# 4BUF_1.net
KiCad netlist of a schematic drawn in EAGLE
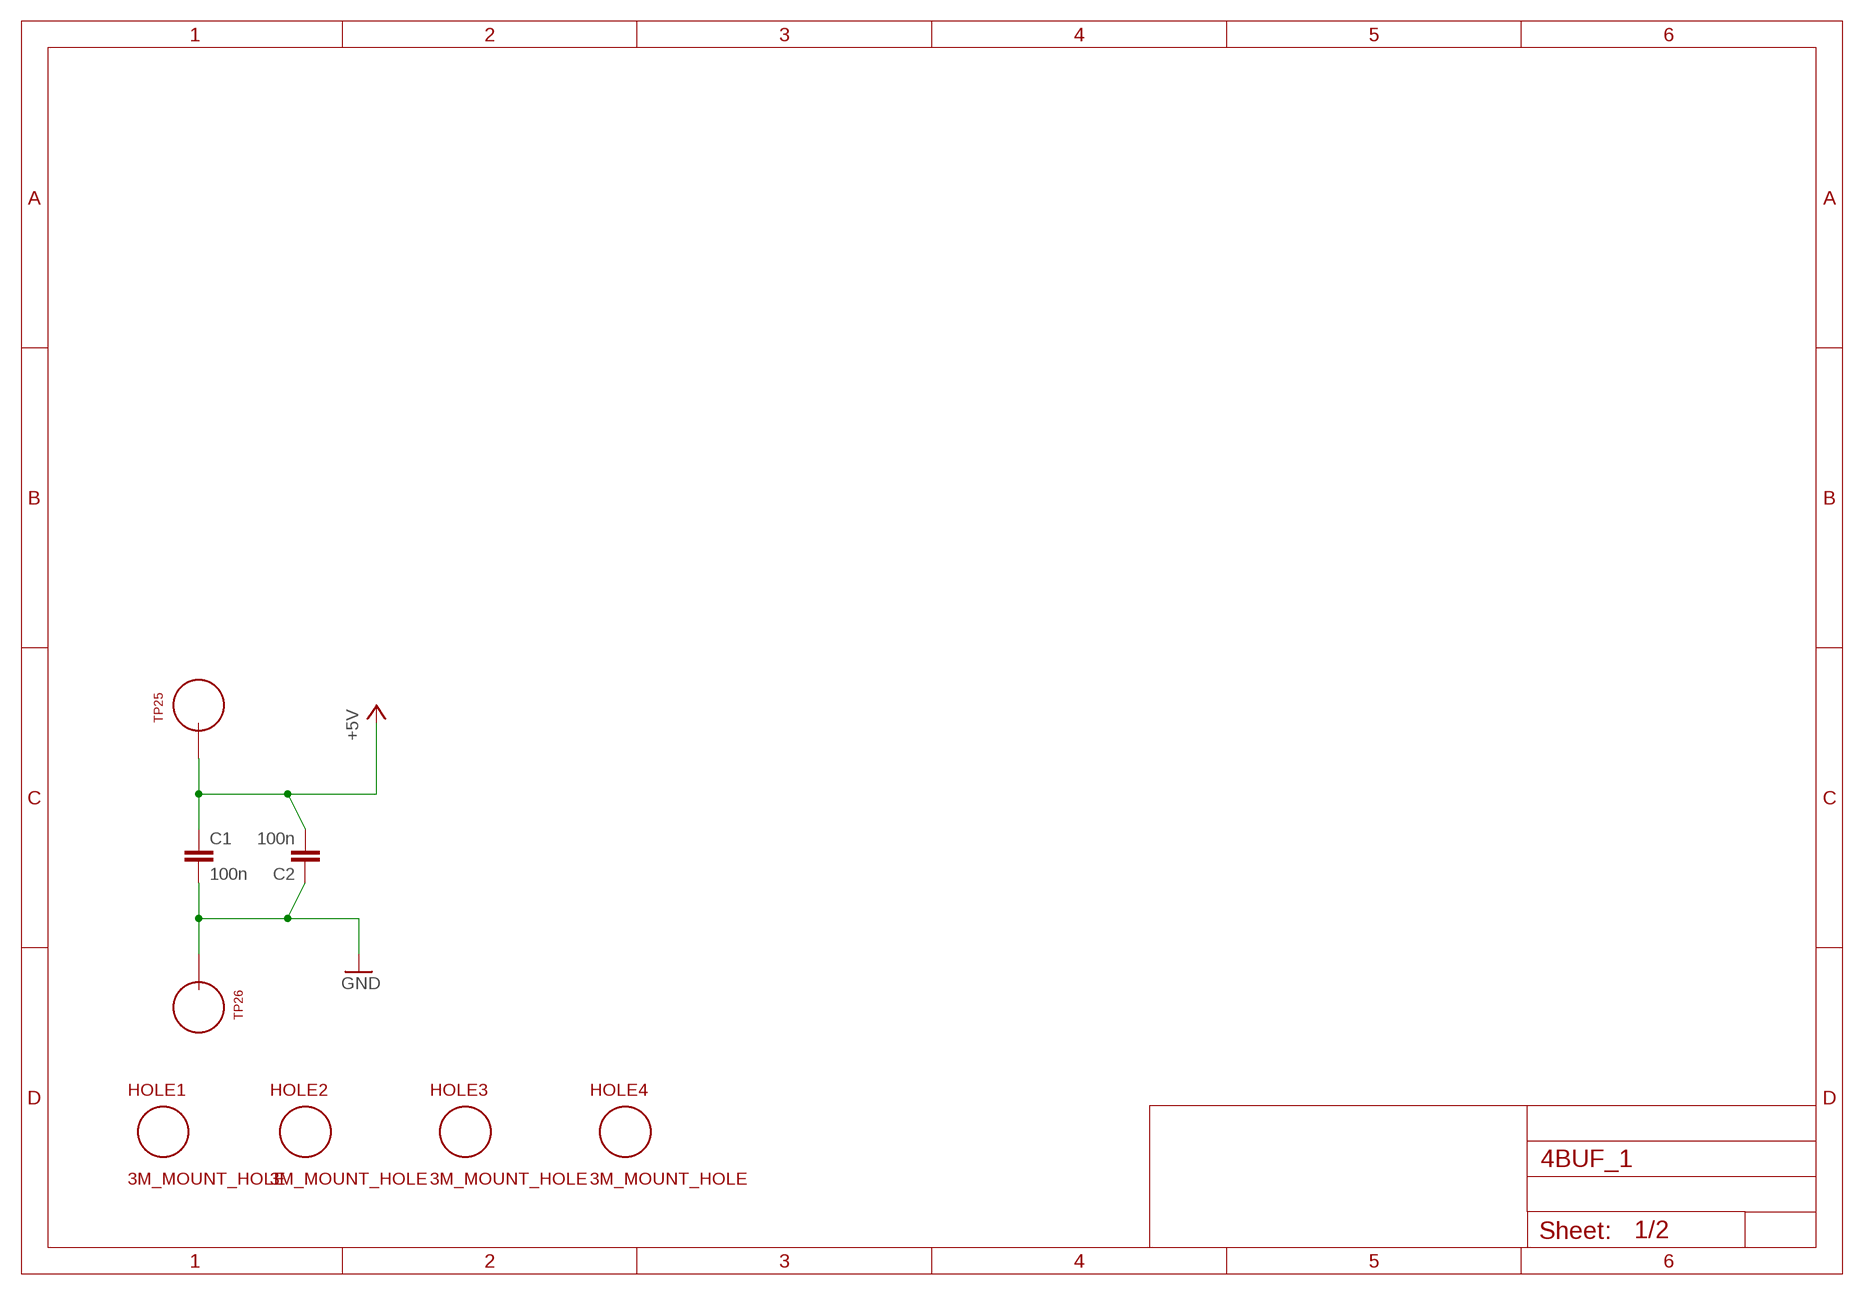
[diagram p0: schematic, sheet 1]
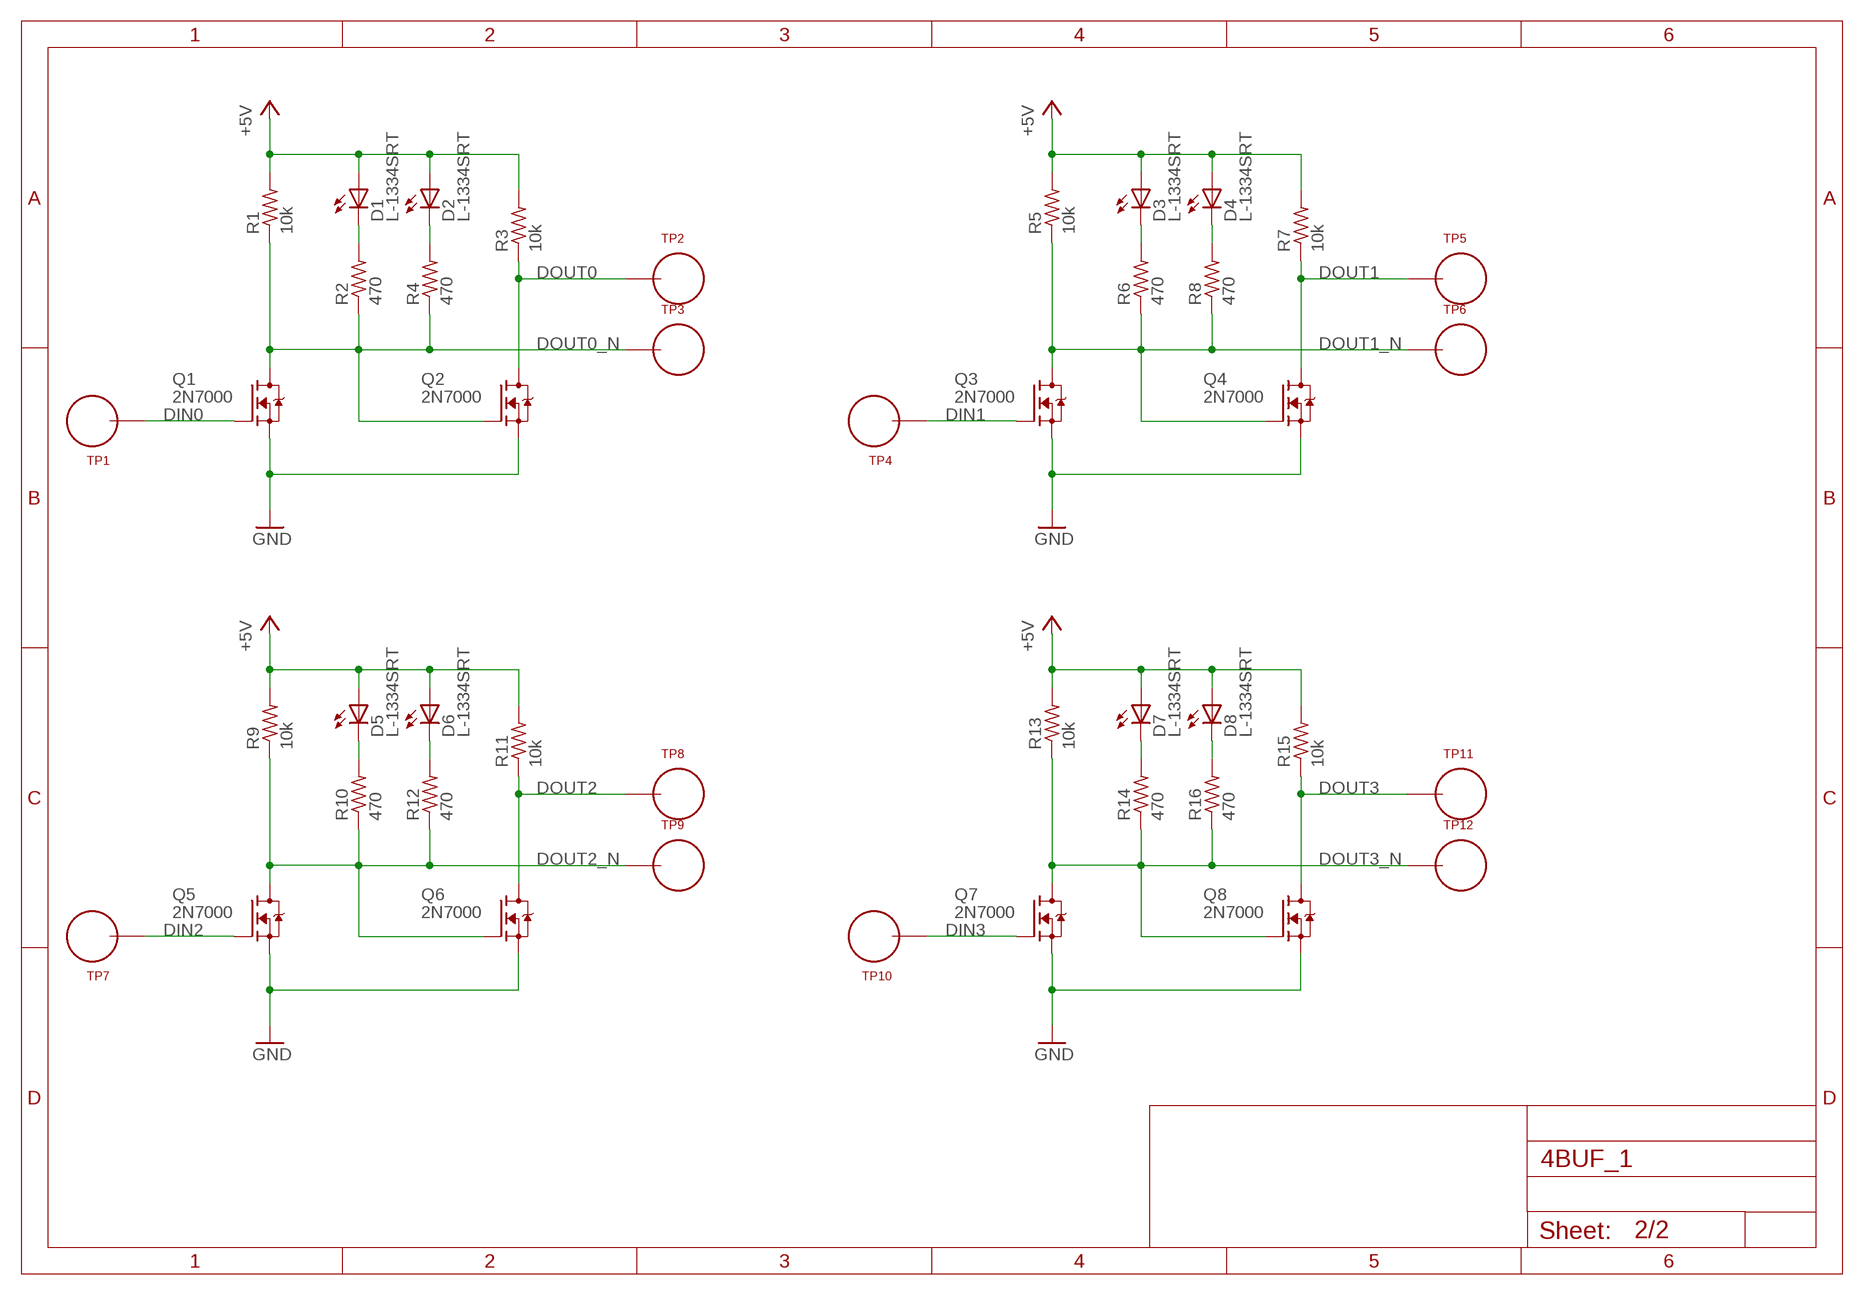
[diagram p1: schematic, sheet 2]

(export (version "E")
  (design (tool "Eeschema 10.0.6"))
  (components
    (comp (ref "C1")
      (value "100n")
      (footprint "eagle-import:CAP_P2INCH")
      (libsource (lib "eagle-import") (part "C_P2INCH"))
    )
    (comp (ref "C2")
      (value "100n")
      (footprint "eagle-import:CAP_P2INCH")
      (libsource (lib "eagle-import") (part "C_P2INCH"))
    )
    (comp (ref "HOLE1")
      (value "3M_MOUNT_HOLE")
      (footprint "eagle-import:3M_HOLE")
      (libsource (lib "eagle-import") (part "3M_MOUNT_HOLE"))
    )
    (comp (ref "HOLE2")
      (value "3M_MOUNT_HOLE")
      (footprint "eagle-import:3M_HOLE")
      (libsource (lib "eagle-import") (part "3M_MOUNT_HOLE"))
    )
    (comp (ref "HOLE3")
      (value "3M_MOUNT_HOLE")
      (footprint "eagle-import:3M_HOLE")
      (libsource (lib "eagle-import") (part "3M_MOUNT_HOLE"))
    )
    (comp (ref "HOLE4")
      (value "3M_MOUNT_HOLE")
      (footprint "eagle-import:3M_HOLE")
      (libsource (lib "eagle-import") (part "3M_MOUNT_HOLE"))
    )
    (comp (ref "TP25")
      (value "TEST_LOOP")
      (footprint "eagle-import:TEST_LOOP")
      (libsource (lib "eagle-import") (part "TEST_LOOP"))
    )
    (comp (ref "TP26")
      (value "TEST_LOOP")
      (footprint "eagle-import:TEST_LOOP")
      (libsource (lib "eagle-import") (part "TEST_LOOP"))
    )
    (comp (ref "D1")
      (value "L-1334SRT")
      (footprint "eagle-import:LED3MM")
      (libsource (lib "eagle-import") (part "L-1334SRT"))
    )
    (comp (ref "D2")
      (value "L-1334SRT")
      (footprint "eagle-import:LED3MM")
      (libsource (lib "eagle-import") (part "L-1334SRT"))
    )
    (comp (ref "D3")
      (value "L-1334SRT")
      (footprint "eagle-import:LED3MM")
      (libsource (lib "eagle-import") (part "L-1334SRT"))
    )
    (comp (ref "D4")
      (value "L-1334SRT")
      (footprint "eagle-import:LED3MM")
      (libsource (lib "eagle-import") (part "L-1334SRT"))
    )
    (comp (ref "D5")
      (value "L-1334SRT")
      (footprint "eagle-import:LED3MM")
      (libsource (lib "eagle-import") (part "L-1334SRT"))
    )
    (comp (ref "D6")
      (value "L-1334SRT")
      (footprint "eagle-import:LED3MM")
      (libsource (lib "eagle-import") (part "L-1334SRT"))
    )
    (comp (ref "D7")
      (value "L-1334SRT")
      (footprint "eagle-import:LED3MM")
      (libsource (lib "eagle-import") (part "L-1334SRT"))
    )
    (comp (ref "D8")
      (value "L-1334SRT")
      (footprint "eagle-import:LED3MM")
      (libsource (lib "eagle-import") (part "L-1334SRT"))
    )
    (comp (ref "Q1")
      (value "2N7000")
      (footprint "eagle-import:TO92-DGS")
      (libsource (lib "eagle-import") (part "2N7000"))
    )
    (comp (ref "Q2")
      (value "2N7000")
      (footprint "eagle-import:TO92-DGS")
      (libsource (lib "eagle-import") (part "2N7000"))
    )
    (comp (ref "Q3")
      (value "2N7000")
      (footprint "eagle-import:TO92-DGS")
      (libsource (lib "eagle-import") (part "2N7000"))
    )
    (comp (ref "Q4")
      (value "2N7000")
      (footprint "eagle-import:TO92-DGS")
      (libsource (lib "eagle-import") (part "2N7000"))
    )
    (comp (ref "Q5")
      (value "2N7000")
      (footprint "eagle-import:TO92-DGS")
      (libsource (lib "eagle-import") (part "2N7000"))
    )
    (comp (ref "Q6")
      (value "2N7000")
      (footprint "eagle-import:TO92-DGS")
      (libsource (lib "eagle-import") (part "2N7000"))
    )
    (comp (ref "Q7")
      (value "2N7000")
      (footprint "eagle-import:TO92-DGS")
      (libsource (lib "eagle-import") (part "2N7000"))
    )
    (comp (ref "Q8")
      (value "2N7000")
      (footprint "eagle-import:TO92-DGS")
      (libsource (lib "eagle-import") (part "2N7000"))
    )
    (comp (ref "R1")
      (value "10k")
      (footprint "eagle-import:R_P2INCH")
      (libsource (lib "eagle-import") (part "R_P2INCH"))
    )
    (comp (ref "R2")
      (value "470")
      (footprint "eagle-import:R_P2INCH")
      (libsource (lib "eagle-import") (part "R_P2INCH"))
    )
    (comp (ref "R3")
      (value "10k")
      (footprint "eagle-import:R_P2INCH")
      (libsource (lib "eagle-import") (part "R_P2INCH"))
    )
    (comp (ref "R4")
      (value "470")
      (footprint "eagle-import:R_P2INCH")
      (libsource (lib "eagle-import") (part "R_P2INCH"))
    )
    (comp (ref "R5")
      (value "10k")
      (footprint "eagle-import:R_P2INCH")
      (libsource (lib "eagle-import") (part "R_P2INCH"))
    )
    (comp (ref "R6")
      (value "470")
      (footprint "eagle-import:R_P2INCH")
      (libsource (lib "eagle-import") (part "R_P2INCH"))
    )
    (comp (ref "R7")
      (value "10k")
      (footprint "eagle-import:R_P2INCH")
      (libsource (lib "eagle-import") (part "R_P2INCH"))
    )
    (comp (ref "R8")
      (value "470")
      (footprint "eagle-import:R_P2INCH")
      (libsource (lib "eagle-import") (part "R_P2INCH"))
    )
    (comp (ref "R9")
      (value "10k")
      (footprint "eagle-import:R_P2INCH")
      (libsource (lib "eagle-import") (part "R_P2INCH"))
    )
    (comp (ref "R10")
      (value "470")
      (footprint "eagle-import:R_P2INCH")
      (libsource (lib "eagle-import") (part "R_P2INCH"))
    )
    (comp (ref "R11")
      (value "10k")
      (footprint "eagle-import:R_P2INCH")
      (libsource (lib "eagle-import") (part "R_P2INCH"))
    )
    (comp (ref "R12")
      (value "470")
      (footprint "eagle-import:R_P2INCH")
      (libsource (lib "eagle-import") (part "R_P2INCH"))
    )
    (comp (ref "R13")
      (value "10k")
      (footprint "eagle-import:R_P2INCH")
      (libsource (lib "eagle-import") (part "R_P2INCH"))
    )
    (comp (ref "R14")
      (value "470")
      (footprint "eagle-import:R_P2INCH")
      (libsource (lib "eagle-import") (part "R_P2INCH"))
    )
    (comp (ref "R15")
      (value "10k")
      (footprint "eagle-import:R_P2INCH")
      (libsource (lib "eagle-import") (part "R_P2INCH"))
    )
    (comp (ref "R16")
      (value "470")
      (footprint "eagle-import:R_P2INCH")
      (libsource (lib "eagle-import") (part "R_P2INCH"))
    )
    (comp (ref "TP1")
      (value "TEST_LOOP")
      (footprint "eagle-import:TEST_LOOP")
      (libsource (lib "eagle-import") (part "TEST_LOOP"))
    )
    (comp (ref "TP2")
      (value "TEST_LOOP")
      (footprint "eagle-import:TEST_LOOP")
      (libsource (lib "eagle-import") (part "TEST_LOOP"))
    )
    (comp (ref "TP3")
      (value "TEST_LOOP")
      (footprint "eagle-import:TEST_LOOP")
      (libsource (lib "eagle-import") (part "TEST_LOOP"))
    )
    (comp (ref "TP4")
      (value "TEST_LOOP")
      (footprint "eagle-import:TEST_LOOP")
      (libsource (lib "eagle-import") (part "TEST_LOOP"))
    )
    (comp (ref "TP5")
      (value "TEST_LOOP")
      (footprint "eagle-import:TEST_LOOP")
      (libsource (lib "eagle-import") (part "TEST_LOOP"))
    )
    (comp (ref "TP6")
      (value "TEST_LOOP")
      (footprint "eagle-import:TEST_LOOP")
      (libsource (lib "eagle-import") (part "TEST_LOOP"))
    )
    (comp (ref "TP7")
      (value "TEST_LOOP")
      (footprint "eagle-import:TEST_LOOP")
      (libsource (lib "eagle-import") (part "TEST_LOOP"))
    )
    (comp (ref "TP8")
      (value "TEST_LOOP")
      (footprint "eagle-import:TEST_LOOP")
      (libsource (lib "eagle-import") (part "TEST_LOOP"))
    )
    (comp (ref "TP9")
      (value "TEST_LOOP")
      (footprint "eagle-import:TEST_LOOP")
      (libsource (lib "eagle-import") (part "TEST_LOOP"))
    )
    (comp (ref "TP10")
      (value "TEST_LOOP")
      (footprint "eagle-import:TEST_LOOP")
      (libsource (lib "eagle-import") (part "TEST_LOOP"))
    )
    (comp (ref "TP11")
      (value "TEST_LOOP")
      (footprint "eagle-import:TEST_LOOP")
      (libsource (lib "eagle-import") (part "TEST_LOOP"))
    )
    (comp (ref "TP12")
      (value "TEST_LOOP")
      (footprint "eagle-import:TEST_LOOP")
      (libsource (lib "eagle-import") (part "TEST_LOOP"))
    )
  )
  (nets
    (net (code "1") (name "+5V") (class "Default")
      (node (ref "C1") (pin "1") (pinfunction "1_1") (pintype "passive"))
      (node (ref "C2") (pin "2") (pinfunction "2_2") (pintype "passive"))
      (node (ref "D1") (pin "A") (pinfunction "A_A") (pintype "passive"))
      (node (ref "D2") (pin "A") (pinfunction "A_A") (pintype "passive"))
      (node (ref "D3") (pin "A") (pinfunction "A_A") (pintype "passive"))
      (node (ref "D4") (pin "A") (pinfunction "A_A") (pintype "passive"))
      (node (ref "D5") (pin "A") (pinfunction "A_A") (pintype "passive"))
      (node (ref "D6") (pin "A") (pinfunction "A_A") (pintype "passive"))
      (node (ref "D7") (pin "A") (pinfunction "A_A") (pintype "passive"))
      (node (ref "D8") (pin "A") (pinfunction "A_A") (pintype "passive"))
      (node (ref "R1") (pin "2") (pinfunction "2_2") (pintype "passive"))
      (node (ref "R11") (pin "2") (pinfunction "2_2") (pintype "passive"))
      (node (ref "R13") (pin "2") (pinfunction "2_2") (pintype "passive"))
      (node (ref "R15") (pin "2") (pinfunction "2_2") (pintype "passive"))
      (node (ref "R3") (pin "2") (pinfunction "2_2") (pintype "passive"))
      (node (ref "R5") (pin "2") (pinfunction "2_2") (pintype "passive"))
      (node (ref "R7") (pin "2") (pinfunction "2_2") (pintype "passive"))
      (node (ref "R9") (pin "2") (pinfunction "2_2") (pintype "passive"))
      (node (ref "TP25") (pin "P$1") (pinfunction "P$1_P$1") (pintype "bidirectional"))
    )
    (net (code "2") (name "DIN0") (class "Default")
      (node (ref "Q1") (pin "G") (pinfunction "G_G") (pintype "passive"))
      (node (ref "TP1") (pin "P$1") (pinfunction "P$1_P$1") (pintype "bidirectional"))
    )
    (net (code "3") (name "DIN1") (class "Default")
      (node (ref "Q3") (pin "G") (pinfunction "G_G") (pintype "passive"))
      (node (ref "TP4") (pin "P$1") (pinfunction "P$1_P$1") (pintype "bidirectional"))
    )
    (net (code "4") (name "DIN2") (class "Default")
      (node (ref "Q5") (pin "G") (pinfunction "G_G") (pintype "passive"))
      (node (ref "TP7") (pin "P$1") (pinfunction "P$1_P$1") (pintype "bidirectional"))
    )
    (net (code "5") (name "DIN3") (class "Default")
      (node (ref "Q7") (pin "G") (pinfunction "G_G") (pintype "passive"))
      (node (ref "TP10") (pin "P$1") (pinfunction "P$1_P$1") (pintype "bidirectional"))
    )
    (net (code "6") (name "DOUT0") (class "Default")
      (node (ref "Q2") (pin "D") (pinfunction "D_D") (pintype "passive"))
      (node (ref "R3") (pin "1") (pinfunction "1_1") (pintype "passive"))
      (node (ref "TP2") (pin "P$1") (pinfunction "P$1_P$1") (pintype "bidirectional"))
    )
    (net (code "7") (name "DOUT0_N") (class "Default")
      (node (ref "Q1") (pin "D") (pinfunction "D_D") (pintype "passive"))
      (node (ref "Q2") (pin "G") (pinfunction "G_G") (pintype "passive"))
      (node (ref "R1") (pin "1") (pinfunction "1_1") (pintype "passive"))
      (node (ref "R2") (pin "1") (pinfunction "1_1") (pintype "passive"))
      (node (ref "R4") (pin "1") (pinfunction "1_1") (pintype "passive"))
      (node (ref "TP3") (pin "P$1") (pinfunction "P$1_P$1") (pintype "bidirectional"))
    )
    (net (code "8") (name "DOUT1") (class "Default")
      (node (ref "Q4") (pin "D") (pinfunction "D_D") (pintype "passive"))
      (node (ref "R7") (pin "1") (pinfunction "1_1") (pintype "passive"))
      (node (ref "TP5") (pin "P$1") (pinfunction "P$1_P$1") (pintype "bidirectional"))
    )
    (net (code "9") (name "DOUT1_N") (class "Default")
      (node (ref "Q3") (pin "D") (pinfunction "D_D") (pintype "passive"))
      (node (ref "Q4") (pin "G") (pinfunction "G_G") (pintype "passive"))
      (node (ref "R5") (pin "1") (pinfunction "1_1") (pintype "passive"))
      (node (ref "R6") (pin "1") (pinfunction "1_1") (pintype "passive"))
      (node (ref "R8") (pin "1") (pinfunction "1_1") (pintype "passive"))
      (node (ref "TP6") (pin "P$1") (pinfunction "P$1_P$1") (pintype "bidirectional"))
    )
    (net (code "10") (name "DOUT2") (class "Default")
      (node (ref "Q6") (pin "D") (pinfunction "D_D") (pintype "passive"))
      (node (ref "R11") (pin "1") (pinfunction "1_1") (pintype "passive"))
      (node (ref "TP8") (pin "P$1") (pinfunction "P$1_P$1") (pintype "bidirectional"))
    )
    (net (code "11") (name "DOUT2_N") (class "Default")
      (node (ref "Q5") (pin "D") (pinfunction "D_D") (pintype "passive"))
      (node (ref "Q6") (pin "G") (pinfunction "G_G") (pintype "passive"))
      (node (ref "R10") (pin "1") (pinfunction "1_1") (pintype "passive"))
      (node (ref "R12") (pin "1") (pinfunction "1_1") (pintype "passive"))
      (node (ref "R9") (pin "1") (pinfunction "1_1") (pintype "passive"))
      (node (ref "TP9") (pin "P$1") (pinfunction "P$1_P$1") (pintype "bidirectional"))
    )
    (net (code "12") (name "DOUT3") (class "Default")
      (node (ref "Q8") (pin "D") (pinfunction "D_D") (pintype "passive"))
      (node (ref "R15") (pin "1") (pinfunction "1_1") (pintype "passive"))
      (node (ref "TP11") (pin "P$1") (pinfunction "P$1_P$1") (pintype "bidirectional"))
    )
    (net (code "13") (name "DOUT3_N") (class "Default")
      (node (ref "Q7") (pin "D") (pinfunction "D_D") (pintype "passive"))
      (node (ref "Q8") (pin "G") (pinfunction "G_G") (pintype "passive"))
      (node (ref "R13") (pin "1") (pinfunction "1_1") (pintype "passive"))
      (node (ref "R14") (pin "1") (pinfunction "1_1") (pintype "passive"))
      (node (ref "R16") (pin "1") (pinfunction "1_1") (pintype "passive"))
      (node (ref "TP12") (pin "P$1") (pinfunction "P$1_P$1") (pintype "bidirectional"))
    )
    (net (code "14") (name "GND") (class "Default")
      (node (ref "C1") (pin "2") (pinfunction "2_2") (pintype "passive"))
      (node (ref "C2") (pin "1") (pinfunction "1_1") (pintype "passive"))
      (node (ref "Q1") (pin "S") (pinfunction "S_S") (pintype "passive"))
      (node (ref "Q2") (pin "S") (pinfunction "S_S") (pintype "passive"))
      (node (ref "Q3") (pin "S") (pinfunction "S_S") (pintype "passive"))
      (node (ref "Q4") (pin "S") (pinfunction "S_S") (pintype "passive"))
      (node (ref "Q5") (pin "S") (pinfunction "S_S") (pintype "passive"))
      (node (ref "Q6") (pin "S") (pinfunction "S_S") (pintype "passive"))
      (node (ref "Q7") (pin "S") (pinfunction "S_S") (pintype "passive"))
      (node (ref "Q8") (pin "S") (pinfunction "S_S") (pintype "passive"))
      (node (ref "TP26") (pin "P$1") (pinfunction "P$1_P$1") (pintype "bidirectional"))
    )
    (net (code "15") (name "Net-(D1-C)") (class "Default")
      (node (ref "D1") (pin "K") (pinfunction "C_K") (pintype "passive"))
      (node (ref "R2") (pin "2") (pinfunction "2_2") (pintype "passive"))
    )
    (net (code "16") (name "Net-(D2-C)") (class "Default")
      (node (ref "D2") (pin "K") (pinfunction "C_K") (pintype "passive"))
      (node (ref "R4") (pin "2") (pinfunction "2_2") (pintype "passive"))
    )
    (net (code "17") (name "Net-(D3-C)") (class "Default")
      (node (ref "D3") (pin "K") (pinfunction "C_K") (pintype "passive"))
      (node (ref "R6") (pin "2") (pinfunction "2_2") (pintype "passive"))
    )
    (net (code "18") (name "Net-(D4-C)") (class "Default")
      (node (ref "D4") (pin "K") (pinfunction "C_K") (pintype "passive"))
      (node (ref "R8") (pin "2") (pinfunction "2_2") (pintype "passive"))
    )
    (net (code "19") (name "Net-(D5-C)") (class "Default")
      (node (ref "D5") (pin "K") (pinfunction "C_K") (pintype "passive"))
      (node (ref "R10") (pin "2") (pinfunction "2_2") (pintype "passive"))
    )
    (net (code "20") (name "Net-(D6-C)") (class "Default")
      (node (ref "D6") (pin "K") (pinfunction "C_K") (pintype "passive"))
      (node (ref "R12") (pin "2") (pinfunction "2_2") (pintype "passive"))
    )
    (net (code "21") (name "Net-(D7-C)") (class "Default")
      (node (ref "D7") (pin "K") (pinfunction "C_K") (pintype "passive"))
      (node (ref "R14") (pin "2") (pinfunction "2_2") (pintype "passive"))
    )
    (net (code "22") (name "Net-(D8-C)") (class "Default")
      (node (ref "D8") (pin "K") (pinfunction "C_K") (pintype "passive"))
      (node (ref "R16") (pin "2") (pinfunction "2_2") (pintype "passive"))
    )
  )
)
